# RS422.net
KiCad netlist of a schematic drawn in Altium Designer
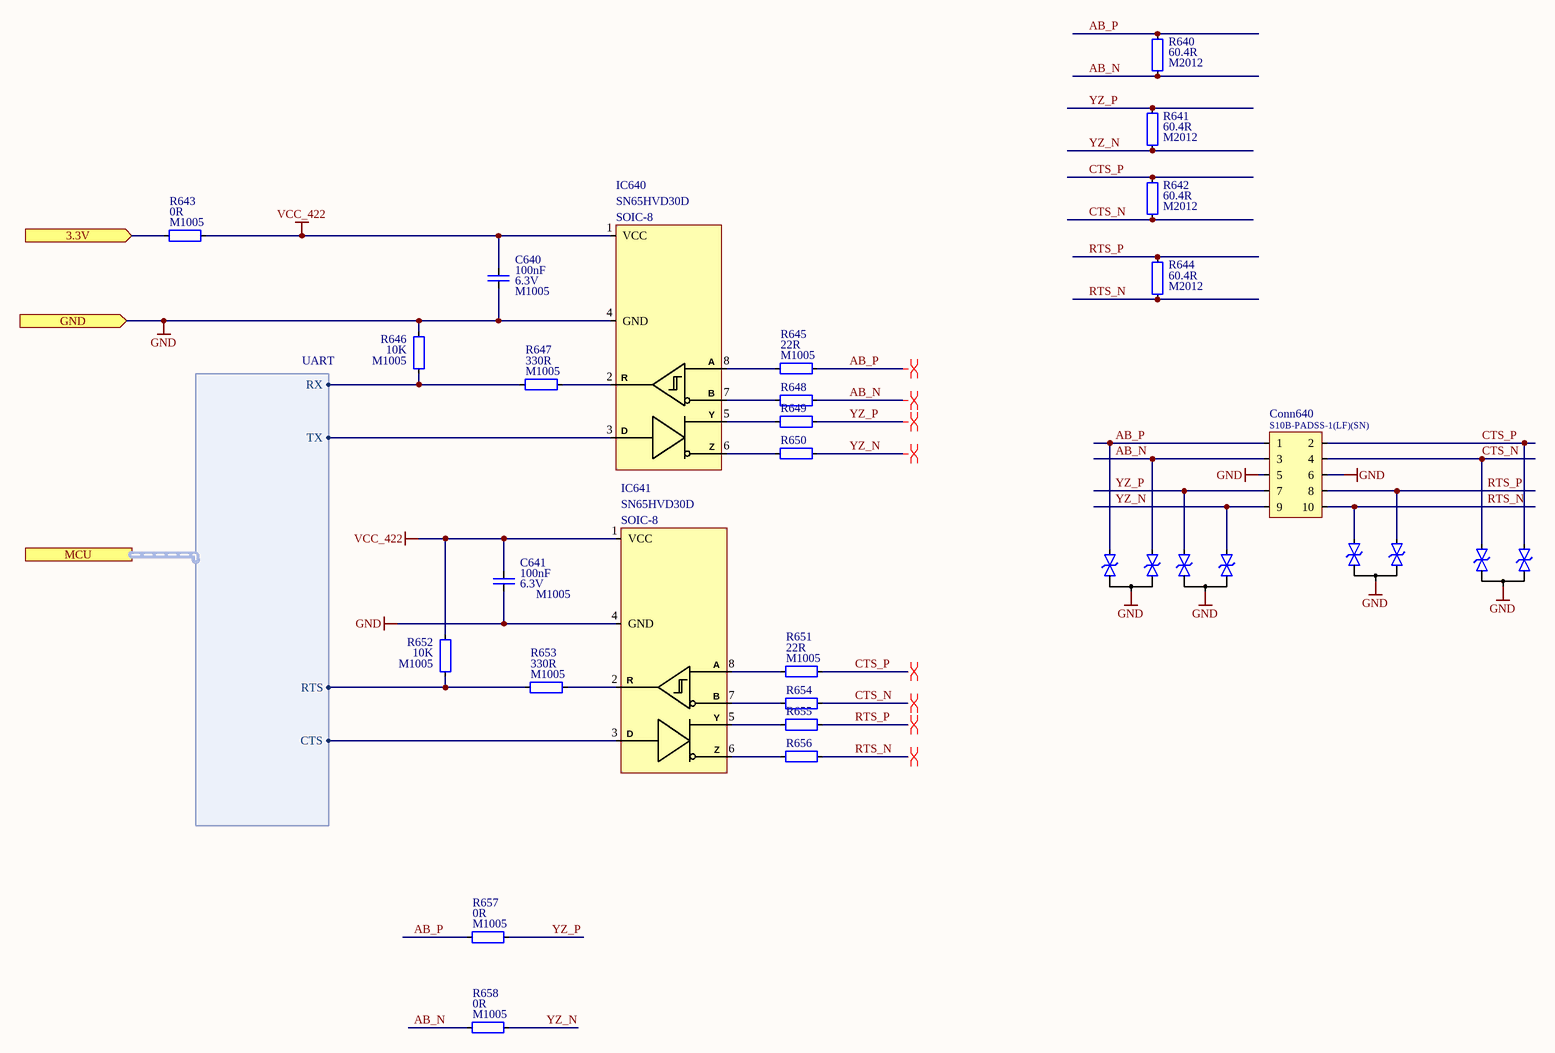
[diagram p0: RS422.SchDoc]

(export (version "E")
  (design (tool "Eeschema 10.0.6"))
  (components
    (comp (ref "C640")
      (value "100nF")
      (footprint "Capacitor_Ceramic_M1005_I0402")
      (description "Cap, Cer, 100nF, 6.3V, M1005")
      (fields
        (field (name "VOLTAGE") "6.3V")
        (field (name "MANUFACTURER PART NUMBER") "04026D104KAT4A")
        (field (name "MANUFACTURER") "Kyocera")
        (field (name "PACKAGE") "M1005")
      )
      (libsource (lib "Capacitor") (part "Capacitor_Ceramic"))
    )
    (comp (ref "C641")
      (value "100nF")
      (footprint "Capacitor_Ceramic_M1005_I0402")
      (description "Cap, Cer, 100nF, 6.3V, M1005")
      (fields
        (field (name "VOLTAGE") "6.3V")
        (field (name "MANUFACTURER PART NUMBER") "04026D104KAT4A")
        (field (name "MANUFACTURER") "Kyocera")
        (field (name "PACKAGE") "M1005")
      )
      (libsource (lib "Capacitor") (part "Capacitor_Ceramic"))
    )
    (comp (ref "Conn640")
      (value "Connector - 10P")
      (footprint "Connector, S10B-PADSS-1")
      (description "Conn, JST, 10P, TH, PAD, Side Entry")
      (fields
        (field (name "MANUFACTURER") "JST")
        (field (name "MANUFACTURER PART NUMBER") "S10B-PADSS-1(LF)(SN)")
      )
      (libsource (lib "Connector - JST") (part "Connector - 10P"))
    )
    (comp (ref "IC640")
      (value "RS422 - Texas, SN65HVD30D")
      (footprint "SOIC-8, NB")
      (description "IC, Interface, RS422, SOIC-8")
      (fields
        (field (name "MANUFACTURER") "Texas")
        (field (name "MANUFACTURER PART NUMBER") "SN65HVD30D")
        (field (name "PACKAGE") "SOIC-8")
      )
      (libsource (lib "IC-Interface") (part "RS422 - Texas, SN65HVD30D"))
    )
    (comp (ref "IC641")
      (value "RS422 - Texas, SN65HVD30D")
      (footprint "SOIC-8, NB")
      (description "IC, Interface, RS422, SOIC-8")
      (fields
        (field (name "MANUFACTURER") "Texas")
        (field (name "MANUFACTURER PART NUMBER") "SN65HVD30D")
        (field (name "PACKAGE") "SOIC-8")
      )
      (libsource (lib "IC-Interface") (part "RS422 - Texas, SN65HVD30D"))
    )
    (comp (ref "R640")
      (value "60.4R")
      (footprint "Resistor_Smd_M2012_I0805")
      (description "Res, 60.4R, 1%, M1005")
      (fields
        (field (name "TOLERANCE") "1%")
        (field (name "MANUFACTURER") "Yageo")
        (field (name "PACKAGE") "M2012")
      )
      (libsource (lib "Resistor") (part "Resistor"))
    )
    (comp (ref "R641")
      (value "60.4R")
      (footprint "Resistor_Smd_M2012_I0805")
      (description "Res, 60.4R, 1%, M1005")
      (fields
        (field (name "TOLERANCE") "1%")
        (field (name "MANUFACTURER") "Yageo")
        (field (name "PACKAGE") "M2012")
      )
      (libsource (lib "Resistor") (part "Resistor"))
    )
    (comp (ref "R642")
      (value "60.4R")
      (footprint "Resistor_Smd_M2012_I0805")
      (description "Res, 60.4R, 1%, M1005")
      (fields
        (field (name "TOLERANCE") "1%")
        (field (name "MANUFACTURER") "Yageo")
        (field (name "PACKAGE") "M2012")
      )
      (libsource (lib "Resistor") (part "Resistor"))
    )
    (comp (ref "R643")
      (value "0R")
      (footprint "Resistor_Smd_M1005_I0402")
      (description "Res, 0R, M1005")
      (fields
        (field (name "MANUFACTURER") "Yageo")
        (field (name "MANUFACTURER PART NUMBER") "RC0402FR-070RL")
        (field (name "PACKAGE") "M1005")
      )
      (libsource (lib "Resistor") (part "Resistor"))
    )
    (comp (ref "R644")
      (value "60.4R")
      (footprint "Resistor_Smd_M2012_I0805")
      (description "Res, 60.4R, 1%, M1005")
      (fields
        (field (name "TOLERANCE") "1%")
        (field (name "MANUFACTURER") "Yageo")
        (field (name "PACKAGE") "M2012")
      )
      (libsource (lib "Resistor") (part "Resistor"))
    )
    (comp (ref "R645")
      (value "22R")
      (footprint "Resistor_Smd_M1005_I0402")
      (description "Res, 22R, 1%, M1005")
      (fields
        (field (name "TOLERANCE") "1%")
        (field (name "MANUFACTURER") "Yageo")
        (field (name "PACKAGE") "M1005")
      )
      (libsource (lib "Resistor") (part "Resistor"))
    )
    (comp (ref "R646")
      (value "10K")
      (footprint "Resistor_Smd_M1005_I0402")
      (description "Res, 10K, 1%, M1005")
      (fields
        (field (name "TOLERANCE") "1%")
        (field (name "MANUFACTURER") "Yageo")
        (field (name "PACKAGE") "M1005")
      )
      (libsource (lib "Resistor") (part "Resistor"))
    )
    (comp (ref "R647")
      (value "330R")
      (footprint "Resistor_Smd_M1005_I0402")
      (description "Res, 330R, 1%, M1005")
      (fields
        (field (name "TOLERANCE") "1%")
        (field (name "MANUFACTURER") "Yageo")
        (field (name "PACKAGE") "M1005")
      )
      (libsource (lib "Resistor") (part "Resistor"))
    )
    (comp (ref "R648")
      (value "Resistor")
      (footprint "Resistor_Smd_M1005_I0402")
      (description "Res, 22R, 1%, M1005")
      (fields (field (name "TOLERANCE") "1%") (field (name "MANUFACTURER") "Yageo"))
      (libsource (lib "Resistor") (part "Resistor"))
    )
    (comp (ref "R649")
      (value "Resistor")
      (footprint "Resistor_Smd_M1005_I0402")
      (description "Res, 22R, 1%, M1005")
      (fields (field (name "TOLERANCE") "1%") (field (name "MANUFACTURER") "Yageo"))
      (libsource (lib "Resistor") (part "Resistor"))
    )
    (comp (ref "R650")
      (value "Resistor")
      (footprint "Resistor_Smd_M1005_I0402")
      (description "Res, 22R, 1%, M1005")
      (fields (field (name "TOLERANCE") "1%") (field (name "MANUFACTURER") "Yageo"))
      (libsource (lib "Resistor") (part "Resistor"))
    )
    (comp (ref "R651")
      (value "22R")
      (footprint "Resistor_Smd_M1005_I0402")
      (description "Res, 22R, 1%, M1005")
      (fields
        (field (name "TOLERANCE") "1%")
        (field (name "MANUFACTURER") "Yageo")
        (field (name "PACKAGE") "M1005")
      )
      (libsource (lib "Resistor") (part "Resistor"))
    )
    (comp (ref "R652")
      (value "10K")
      (footprint "Resistor_Smd_M1005_I0402")
      (description "Res, 10K, 1%, M1005")
      (fields
        (field (name "TOLERANCE") "1%")
        (field (name "MANUFACTURER") "Yageo")
        (field (name "PACKAGE") "M1005")
      )
      (libsource (lib "Resistor") (part "Resistor"))
    )
    (comp (ref "R653")
      (value "330R")
      (footprint "Resistor_Smd_M1005_I0402")
      (description "Res, 330R, 1%, M1005")
      (fields
        (field (name "TOLERANCE") "1%")
        (field (name "MANUFACTURER") "Yageo")
        (field (name "PACKAGE") "M1005")
      )
      (libsource (lib "Resistor") (part "Resistor"))
    )
    (comp (ref "R654")
      (value "Resistor")
      (footprint "Resistor_Smd_M1005_I0402")
      (description "Res, 22R, 1%, M1005")
      (fields (field (name "TOLERANCE") "1%") (field (name "MANUFACTURER") "Yageo"))
      (libsource (lib "Resistor") (part "Resistor"))
    )
    (comp (ref "R655")
      (value "Resistor")
      (footprint "Resistor_Smd_M1005_I0402")
      (description "Res, 22R, 1%, M1005")
      (fields (field (name "TOLERANCE") "1%") (field (name "MANUFACTURER") "Yageo"))
      (libsource (lib "Resistor") (part "Resistor"))
    )
    (comp (ref "R656")
      (value "Resistor")
      (footprint "Resistor_Smd_M1005_I0402")
      (description "Res, 22R, 1%, M1005")
      (fields (field (name "TOLERANCE") "1%") (field (name "MANUFACTURER") "Yageo"))
      (libsource (lib "Resistor") (part "Resistor"))
    )
    (comp (ref "R657")
      (value "0R")
      (footprint "Resistor_Smd_M1005_I0402")
      (description "Res, 0R, M1005")
      (fields
        (field (name "MANUFACTURER") "Yageo")
        (field (name "MANUFACTURER PART NUMBER") "RC0402FR-070RL")
        (field (name "PACKAGE") "M1005")
      )
      (libsource (lib "Resistor") (part "Resistor"))
    )
    (comp (ref "R658")
      (value "0R")
      (footprint "Resistor_Smd_M1005_I0402")
      (description "Res, 0R, M1005")
      (fields
        (field (name "MANUFACTURER") "Yageo")
        (field (name "MANUFACTURER PART NUMBER") "RC0402FR-070RL")
        (field (name "PACKAGE") "M1005")
      )
      (libsource (lib "Resistor") (part "Resistor"))
    )
    (comp (ref "TVS640")
      (value "Diode_Tvs_2P_Bidirectional")
      (footprint "Diode_SOT-23-3_2P_Bidirectional_Type_1")
      (description "TVS, 2P, Bidirectional, 7V/12V, SOT-23-3")
      (fields
        (field (name "MANUFACTURER PART NUMBER") "CDSOT23-SM712")
        (field (name "MANUFACTURER") "Bourns")
      )
      (libsource (lib "Diode") (part "Diode_Tvs_2P_Bidirectional"))
    )
    (comp (ref "TVS641")
      (value "Diode_Tvs_2P_Bidirectional")
      (footprint "Diode_SOT-23-3_2P_Bidirectional_Type_1")
      (description "TVS, 2P, Bidirectional, 7V/12V, SOT-23-3")
      (fields
        (field (name "MANUFACTURER PART NUMBER") "CDSOT23-SM712")
        (field (name "MANUFACTURER") "Bourns")
      )
      (libsource (lib "Diode") (part "Diode_Tvs_2P_Bidirectional"))
    )
    (comp (ref "TVS642")
      (value "Diode_Tvs_2P_Bidirectional")
      (footprint "Diode_SOT-23-3_2P_Bidirectional_Type_1")
      (description "TVS, 2P, Bidirectional, 7V/12V, SOT-23-3")
      (fields
        (field (name "MANUFACTURER PART NUMBER") "CDSOT23-SM712")
        (field (name "MANUFACTURER") "Bourns")
      )
      (libsource (lib "Diode") (part "Diode_Tvs_2P_Bidirectional"))
    )
    (comp (ref "TVS643")
      (value "Diode_Tvs_2P_Bidirectional")
      (footprint "Diode_SOT-23-3_2P_Bidirectional_Type_1")
      (description "TVS, 2P, Bidirectional, 7V/12V, SOT-23-3")
      (fields
        (field (name "MANUFACTURER PART NUMBER") "CDSOT23-SM712")
        (field (name "MANUFACTURER") "Bourns")
      )
      (libsource (lib "Diode") (part "Diode_Tvs_2P_Bidirectional"))
    )
  )
  (nets
    (net (code "2") (name "/3.3V") (class "Default")
      (node (ref "R643") (pin "1") (pinfunction "1_1") (pintype "passive"))
    )
    (net (code "3") (name "/AB_N") (class "Default")
      (node (ref "Conn640") (pin "3") (pinfunction "3_3") (pintype "passive"))
      (node (ref "R640") (pin "2") (pinfunction "2_2") (pintype "passive"))
      (node (ref "R648") (pin "2") (pinfunction "2_2") (pintype "passive"))
      (node (ref "R658") (pin "1") (pinfunction "1_1") (pintype "passive"))
      (node (ref "TVS642") (pin "D2") (pinfunction "D2_D2") (pintype "passive"))
    )
    (net (code "4") (name "/AB_P") (class "Default")
      (node (ref "Conn640") (pin "1") (pinfunction "1_1") (pintype "passive"))
      (node (ref "R640") (pin "1") (pinfunction "1_1") (pintype "passive"))
      (node (ref "R645") (pin "2") (pinfunction "2_2") (pintype "passive"))
      (node (ref "R657") (pin "1") (pinfunction "1_1") (pintype "passive"))
      (node (ref "TVS642") (pin "D1") (pinfunction "D1_D1") (pintype "passive"))
    )
    (net (code "5") (name "/CTS") (class "Default")
      (node (ref "IC641") (pin "3") (pinfunction "D_3") (pintype "passive"))
    )
    (net (code "6") (name "/CTS_N") (class "Default")
      (node (ref "Conn640") (pin "4") (pinfunction "4_4") (pintype "passive"))
      (node (ref "R642") (pin "2") (pinfunction "2_2") (pintype "passive"))
      (node (ref "R654") (pin "2") (pinfunction "2_2") (pintype "passive"))
      (node (ref "TVS641") (pin "D1") (pinfunction "D1_D1") (pintype "passive"))
    )
    (net (code "7") (name "/CTS_P") (class "Default")
      (node (ref "Conn640") (pin "2") (pinfunction "2_2") (pintype "passive"))
      (node (ref "R642") (pin "1") (pinfunction "1_1") (pintype "passive"))
      (node (ref "R651") (pin "2") (pinfunction "2_2") (pintype "passive"))
      (node (ref "TVS641") (pin "D2") (pinfunction "D2_D2") (pintype "passive"))
    )
    (net (code "8") (name "/RTS") (class "Default")
      (node (ref "R652") (pin "2") (pinfunction "2_2") (pintype "passive"))
      (node (ref "R653") (pin "1") (pinfunction "1_1") (pintype "passive"))
    )
    (net (code "9") (name "/RTS_N") (class "Default")
      (node (ref "Conn640") (pin "10") (pinfunction "10_10") (pintype "passive"))
      (node (ref "R644") (pin "2") (pinfunction "2_2") (pintype "passive"))
      (node (ref "R656") (pin "2") (pinfunction "2_2") (pintype "passive"))
      (node (ref "TVS640") (pin "D1") (pinfunction "D1_D1") (pintype "passive"))
    )
    (net (code "10") (name "/RTS_P") (class "Default")
      (node (ref "Conn640") (pin "8") (pinfunction "8_8") (pintype "passive"))
      (node (ref "R644") (pin "1") (pinfunction "1_1") (pintype "passive"))
      (node (ref "R655") (pin "2") (pinfunction "2_2") (pintype "passive"))
      (node (ref "TVS640") (pin "D2") (pinfunction "D2_D2") (pintype "passive"))
    )
    (net (code "11") (name "/RX") (class "Default")
      (node (ref "R646") (pin "2") (pinfunction "2_2") (pintype "passive"))
      (node (ref "R647") (pin "1") (pinfunction "1_1") (pintype "passive"))
    )
    (net (code "12") (name "/TX") (class "Default")
      (node (ref "IC640") (pin "3") (pinfunction "D_3") (pintype "passive"))
    )
    (net (code "13") (name "/YZ_N") (class "Default")
      (node (ref "Conn640") (pin "9") (pinfunction "9_9") (pintype "passive"))
      (node (ref "R641") (pin "2") (pinfunction "2_2") (pintype "passive"))
      (node (ref "R650") (pin "2") (pinfunction "2_2") (pintype "passive"))
      (node (ref "R658") (pin "2") (pinfunction "2_2") (pintype "passive"))
      (node (ref "TVS643") (pin "D2") (pinfunction "D2_D2") (pintype "passive"))
    )
    (net (code "14") (name "/YZ_P") (class "Default")
      (node (ref "Conn640") (pin "7") (pinfunction "7_7") (pintype "passive"))
      (node (ref "R641") (pin "1") (pinfunction "1_1") (pintype "passive"))
      (node (ref "R649") (pin "2") (pinfunction "2_2") (pintype "passive"))
      (node (ref "R657") (pin "2") (pinfunction "2_2") (pintype "passive"))
      (node (ref "TVS643") (pin "D1") (pinfunction "D1_D1") (pintype "passive"))
    )
    (net (code "16") (name "GND") (class "Default")
      (node (ref "C640") (pin "2") (pinfunction "2_2") (pintype "passive"))
      (node (ref "C641") (pin "2") (pinfunction "2_2") (pintype "passive"))
      (node (ref "Conn640") (pin "5") (pinfunction "5_5") (pintype "passive"))
      (node (ref "Conn640") (pin "6") (pinfunction "6_6") (pintype "passive"))
      (node (ref "IC640") (pin "4") (pinfunction "GND_4") (pintype "passive"))
      (node (ref "IC641") (pin "4") (pinfunction "GND_4") (pintype "passive"))
      (node (ref "R646") (pin "1") (pinfunction "1_1") (pintype "passive"))
      (node (ref "TVS640") (pin "Common") (pinfunction "Common_Common") (pintype "passive"))
      (node (ref "TVS641") (pin "Common") (pinfunction "Common_Common") (pintype "passive"))
      (node (ref "TVS642") (pin "Common") (pinfunction "Common_Common") (pintype "passive"))
      (node (ref "TVS643") (pin "Common") (pinfunction "Common_Common") (pintype "passive"))
    )
    (net (code "17") (name "Net-(IC640-A)") (class "Default")
      (node (ref "IC640") (pin "8") (pinfunction "A_8") (pintype "passive"))
      (node (ref "R645") (pin "1") (pinfunction "1_1") (pintype "passive"))
    )
    (net (code "18") (name "Net-(IC640-B)") (class "Default")
      (node (ref "IC640") (pin "7") (pinfunction "B_7") (pintype "passive"))
      (node (ref "R648") (pin "1") (pinfunction "1_1") (pintype "passive"))
    )
    (net (code "19") (name "Net-(IC640-R)") (class "Default")
      (node (ref "IC640") (pin "2") (pinfunction "R_2") (pintype "passive"))
      (node (ref "R647") (pin "2") (pinfunction "2_2") (pintype "passive"))
    )
    (net (code "20") (name "Net-(IC640-Y)") (class "Default")
      (node (ref "IC640") (pin "5") (pinfunction "Y_5") (pintype "passive"))
      (node (ref "R649") (pin "1") (pinfunction "1_1") (pintype "passive"))
    )
    (net (code "21") (name "Net-(IC640-Z)") (class "Default")
      (node (ref "IC640") (pin "6") (pinfunction "Z_6") (pintype "passive"))
      (node (ref "R650") (pin "1") (pinfunction "1_1") (pintype "passive"))
    )
    (net (code "22") (name "Net-(IC641-A)") (class "Default")
      (node (ref "IC641") (pin "8") (pinfunction "A_8") (pintype "passive"))
      (node (ref "R651") (pin "1") (pinfunction "1_1") (pintype "passive"))
    )
    (net (code "23") (name "Net-(IC641-B)") (class "Default")
      (node (ref "IC641") (pin "7") (pinfunction "B_7") (pintype "passive"))
      (node (ref "R654") (pin "1") (pinfunction "1_1") (pintype "passive"))
    )
    (net (code "24") (name "Net-(IC641-R)") (class "Default")
      (node (ref "IC641") (pin "2") (pinfunction "R_2") (pintype "passive"))
      (node (ref "R653") (pin "2") (pinfunction "2_2") (pintype "passive"))
    )
    (net (code "25") (name "Net-(IC641-Y)") (class "Default")
      (node (ref "IC641") (pin "5") (pinfunction "Y_5") (pintype "passive"))
      (node (ref "R655") (pin "1") (pinfunction "1_1") (pintype "passive"))
    )
    (net (code "26") (name "Net-(IC641-Z)") (class "Default")
      (node (ref "IC641") (pin "6") (pinfunction "Z_6") (pintype "passive"))
      (node (ref "R656") (pin "1") (pinfunction "1_1") (pintype "passive"))
    )
    (net (code "27") (name "VCC_422") (class "Default")
      (node (ref "C640") (pin "1") (pinfunction "1_1") (pintype "passive"))
      (node (ref "C641") (pin "1") (pinfunction "1_1") (pintype "passive"))
      (node (ref "IC640") (pin "1") (pinfunction "VCC_1") (pintype "passive"))
      (node (ref "IC641") (pin "1") (pinfunction "VCC_1") (pintype "passive"))
      (node (ref "R643") (pin "2") (pinfunction "2_2") (pintype "passive"))
      (node (ref "R652") (pin "1") (pinfunction "1_1") (pintype "passive"))
    )
  )
)
